# transmitter.net
KiCad netlist of a schematic drawn in EAGLE
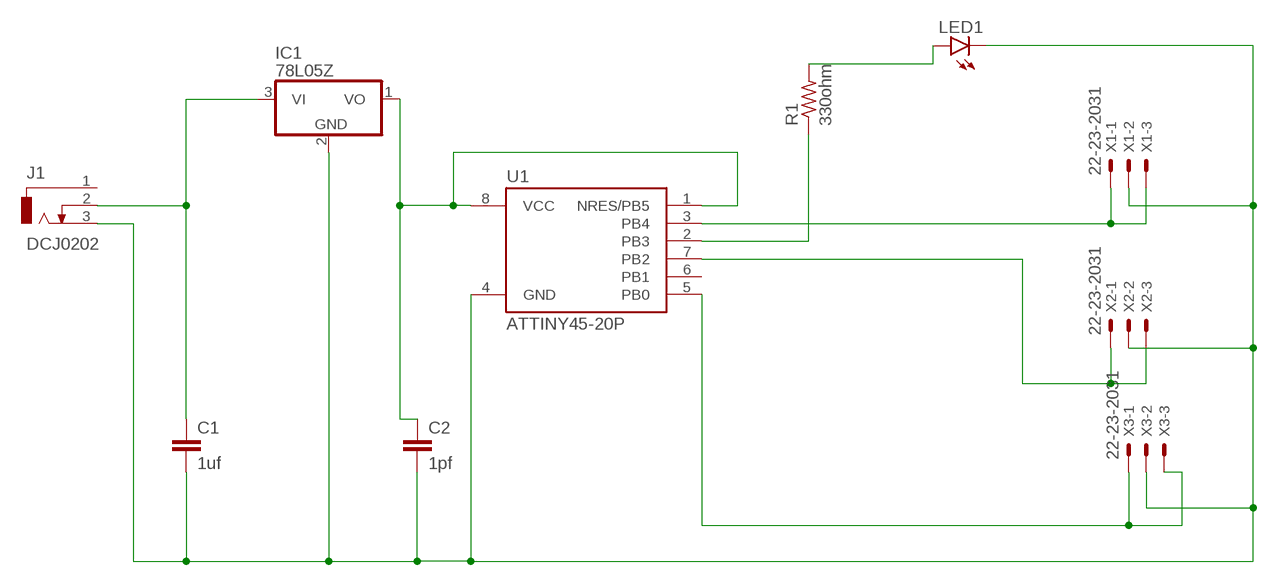
[diagram p0: schematic, sheet 1]

(export (version "E")
  (design (tool "Eeschema 10.0.6"))
  (components
    (comp (ref "C1")
      (value "1uf")
      (footprint "eagle-import:C2.5-2")
      (libsource (lib "eagle-import") (part "C2.5/2"))
    )
    (comp (ref "C2")
      (value "1pf")
      (footprint "eagle-import:C2.5-2")
      (libsource (lib "eagle-import") (part "C2.5/2"))
    )
    (comp (ref "IC1")
      (value "78L05Z")
      (footprint "eagle-import:TO92")
      (libsource (lib "eagle-import") (part "78ZL05"))
    )
    (comp (ref "J1")
      (value "DCJ0202")
      (footprint "eagle-import:DCJ0202")
      (libsource (lib "eagle-import") (part "DCJ0202"))
    )
    (comp (ref "LED1")
      (value "LED3MM")
      (footprint "eagle-import:LED3MM")
      (libsource (lib "eagle-import") (part "LED3MM"))
    )
    (comp (ref "R1")
      (value "330ohm")
      (footprint "eagle-import:0207_10")
      (libsource (lib "eagle-import") (part "R-US_0207/10"))
    )
    (comp (ref "U1")
      (value "ATTINY45-20P")
      (footprint "eagle-import:PDIP08_300MIL")
      (libsource (lib "eagle-import") (part "ATTINY45P-20"))
    )
    (comp (ref "X1")
      (value "22-23-2031")
      (footprint "eagle-import:22-23-2031")
      (fields (field (name "MF") "MOLEX"))
      (libsource (lib "eagle-import") (part "22-23-2031"))
    )
    (comp (ref "X2")
      (value "22-23-2031")
      (footprint "eagle-import:22-23-2031")
      (fields (field (name "MF") "MOLEX"))
      (libsource (lib "eagle-import") (part "22-23-2031"))
    )
    (comp (ref "X3")
      (value "22-23-2031")
      (footprint "eagle-import:22-23-2031")
      (fields (field (name "MF") "MOLEX"))
      (libsource (lib "eagle-import") (part "22-23-2031"))
    )
  )
  (nets
    (net (code "1") (name "Net-(IC1-GND)") (class "Default")
      (node (ref "C1") (pin "2") (pinfunction "2_2") (pintype "passive"))
      (node (ref "C2") (pin "2") (pinfunction "2_2") (pintype "passive"))
      (node (ref "IC1") (pin "2") (pinfunction "GND_2") (pintype "passive"))
      (node (ref "J1") (pin "3") (pinfunction "3_3") (pintype "passive"))
      (node (ref "LED1") (pin "K") (pinfunction "C_K") (pintype "passive"))
      (node (ref "U1") (pin "4") (pinfunction "GND_4") (pintype "power_in"))
      (node (ref "X1") (pin "2") (pinfunction "S_2") (pintype "passive"))
      (node (ref "X2") (pin "2") (pinfunction "S_2") (pintype "passive"))
      (node (ref "X3") (pin "2") (pinfunction "S_2") (pintype "passive"))
    )
    (net (code "2") (name "Net-(IC1-VI)") (class "Default")
      (node (ref "C1") (pin "1") (pinfunction "1_1") (pintype "passive"))
      (node (ref "IC1") (pin "3") (pinfunction "VI_3") (pintype "input"))
      (node (ref "J1") (pin "2") (pinfunction "2_2") (pintype "passive"))
    )
    (net (code "3") (name "Net-(IC1-VO)") (class "Default")
      (node (ref "C2") (pin "1") (pinfunction "1_1") (pintype "passive"))
      (node (ref "IC1") (pin "1") (pinfunction "VO_1") (pintype "passive"))
      (node (ref "U1") (pin "1") (pinfunction "NRES/PB5_1") (pintype "bidirectional"))
      (node (ref "U1") (pin "8") (pinfunction "VCC_8") (pintype "power_in"))
    )
    (net (code "4") (name "Net-(LED1-PadA)") (class "Default")
      (node (ref "LED1") (pin "A") (pinfunction "A_A") (pintype "passive"))
      (node (ref "R1") (pin "2") (pinfunction "2_2") (pintype "passive"))
    )
    (net (code "5") (name "Net-(U1-PB0)") (class "Default")
      (node (ref "U1") (pin "5") (pinfunction "PB0_5") (pintype "bidirectional"))
      (node (ref "X3") (pin "1") (pinfunction "S_1") (pintype "passive"))
      (node (ref "X3") (pin "3") (pinfunction "S_3") (pintype "passive"))
    )
    (net (code "6") (name "Net-(U1-PB2)") (class "Default")
      (node (ref "U1") (pin "7") (pinfunction "PB2_7") (pintype "bidirectional"))
      (node (ref "X2") (pin "1") (pinfunction "S_1") (pintype "passive"))
      (node (ref "X2") (pin "3") (pinfunction "S_3") (pintype "passive"))
    )
    (net (code "7") (name "Net-(U1-PB3)") (class "Default")
      (node (ref "R1") (pin "1") (pinfunction "1_1") (pintype "passive"))
      (node (ref "U1") (pin "2") (pinfunction "PB3_2") (pintype "bidirectional"))
    )
    (net (code "8") (name "Net-(U1-PB4)") (class "Default")
      (node (ref "U1") (pin "3") (pinfunction "PB4_3") (pintype "bidirectional"))
      (node (ref "X1") (pin "1") (pinfunction "S_1") (pintype "passive"))
      (node (ref "X1") (pin "3") (pinfunction "S_3") (pintype "passive"))
    )
    (net (code "9") (name "unconnected-(J1-Pad1)") (class "Default")
      (node (ref "J1") (pin "1") (pinfunction "1_1") (pintype "passive"))
    )
    (net (code "10") (name "unconnected-(U1-PB1-Pad6)") (class "Default")
      (node (ref "U1") (pin "6") (pinfunction "PB1_6") (pintype "bidirectional"))
    )
  )
)
